# MCU_Power.net
KiCad netlist of a schematic drawn in Altium Designer
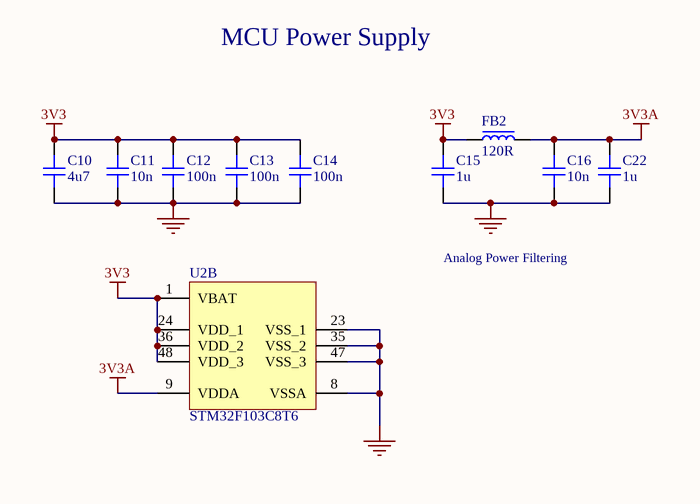
[diagram p0: MCU_Power.SchDoc]

(export (version "E")
  (design (tool "Eeschema 10.0.6"))
  (components
    (comp (ref "C10")
      (value "4u7")
      (footprint "CAP_0603")
      (description "Capacitor SMD 0603")
      (libsource (lib "Schematic-Lib-PhilsLab") (part "CAP_0603"))
    )
    (comp (ref "C11")
      (value "10n")
      (footprint "CAP_0402")
      (description "Capacitor SMD 0402")
      (libsource (lib "Schematic-Lib-PhilsLab") (part "CAP_0402"))
    )
    (comp (ref "C12")
      (value "100n")
      (footprint "CAP_0402")
      (description "Capacitor SMD 0402")
      (libsource (lib "Schematic-Lib-PhilsLab") (part "CAP_0402"))
    )
    (comp (ref "C13")
      (value "100n")
      (footprint "CAP_0402")
      (description "Capacitor SMD 0402")
      (libsource (lib "Schematic-Lib-PhilsLab") (part "CAP_0402"))
    )
    (comp (ref "C14")
      (value "100n")
      (footprint "CAP_0402")
      (description "Capacitor SMD 0402")
      (libsource (lib "Schematic-Lib-PhilsLab") (part "CAP_0402"))
    )
    (comp (ref "C15")
      (value "1u")
      (footprint "CAP_0402")
      (description "Capacitor SMD 0402")
      (libsource (lib "Schematic-Lib-PhilsLab") (part "CAP_0402"))
    )
    (comp (ref "C16")
      (value "10n")
      (footprint "CAP_0402")
      (description "Capacitor SMD 0402")
      (libsource (lib "Schematic-Lib-PhilsLab") (part "CAP_0402"))
    )
    (comp (ref "C22")
      (value "1u")
      (footprint "CAP_0402")
      (description "Capacitor SMD 0402")
      (libsource (lib "Schematic-Lib-PhilsLab") (part "CAP_0402"))
    )
    (comp (ref "FB2")
      (value "120R")
      (footprint "FB_0603")
      (description "Ferrite Bead SMD 0603")
      (libsource (lib "Schematic-Lib-PhilsLab") (part "FB_0603"))
    )
    (comp (ref "U2")
      (value "STM32F103C8T6")
      (footprint "STM-LQFP48_L")
      (libsource (lib "Altium Content Vault") (part "MC-ARM-STM32F103X8_B-SQ48"))
    )
  )
  (nets
    (net (code "1") (name "3V3") (class "Default")
      (node (ref "C10") (pin "2") (pinfunction "2_2") (pintype "passive"))
      (node (ref "C11") (pin "2") (pinfunction "2_2") (pintype "passive"))
      (node (ref "C12") (pin "2") (pinfunction "2_2") (pintype "passive"))
      (node (ref "C13") (pin "2") (pinfunction "2_2") (pintype "passive"))
      (node (ref "C14") (pin "2") (pinfunction "2_2") (pintype "passive"))
      (node (ref "C15") (pin "2") (pinfunction "2_2") (pintype "passive"))
      (node (ref "FB2") (pin "1") (pinfunction "1_1") (pintype "passive"))
      (node (ref "U2") (pin "1") (pinfunction "VBAT_1") (pintype "power_in"))
      (node (ref "U2") (pin "24") (pinfunction "VDD_1_24") (pintype "power_in"))
      (node (ref "U2") (pin "36") (pinfunction "VDD_2_36") (pintype "power_in"))
      (node (ref "U2") (pin "48") (pinfunction "VDD_3_48") (pintype "power_in"))
    )
    (net (code "2") (name "3V3A") (class "Default")
      (node (ref "C16") (pin "2") (pinfunction "2_2") (pintype "passive"))
      (node (ref "C22") (pin "2") (pinfunction "2_2") (pintype "passive"))
      (node (ref "FB2") (pin "2") (pinfunction "2_2") (pintype "passive"))
      (node (ref "U2") (pin "9") (pinfunction "VDDA_9") (pintype "power_in"))
    )
    (net (code "3") (name "GND") (class "Default")
      (node (ref "C10") (pin "1") (pinfunction "1_1") (pintype "passive"))
      (node (ref "C11") (pin "1") (pinfunction "1_1") (pintype "passive"))
      (node (ref "C12") (pin "1") (pinfunction "1_1") (pintype "passive"))
      (node (ref "C13") (pin "1") (pinfunction "1_1") (pintype "passive"))
      (node (ref "C14") (pin "1") (pinfunction "1_1") (pintype "passive"))
      (node (ref "C15") (pin "1") (pinfunction "1_1") (pintype "passive"))
      (node (ref "C16") (pin "1") (pinfunction "1_1") (pintype "passive"))
      (node (ref "C22") (pin "1") (pinfunction "1_1") (pintype "passive"))
      (node (ref "U2") (pin "23") (pinfunction "VSS_1_23") (pintype "power_in"))
      (node (ref "U2") (pin "35") (pinfunction "VSS_2_35") (pintype "power_in"))
      (node (ref "U2") (pin "47") (pinfunction "VSS_3_47") (pintype "power_in"))
      (node (ref "U2") (pin "8") (pinfunction "VSSA_8") (pintype "power_in"))
    )
  )
)
